# MCPv3ULN2803.net
KiCad netlist of a schematic drawn in EAGLE
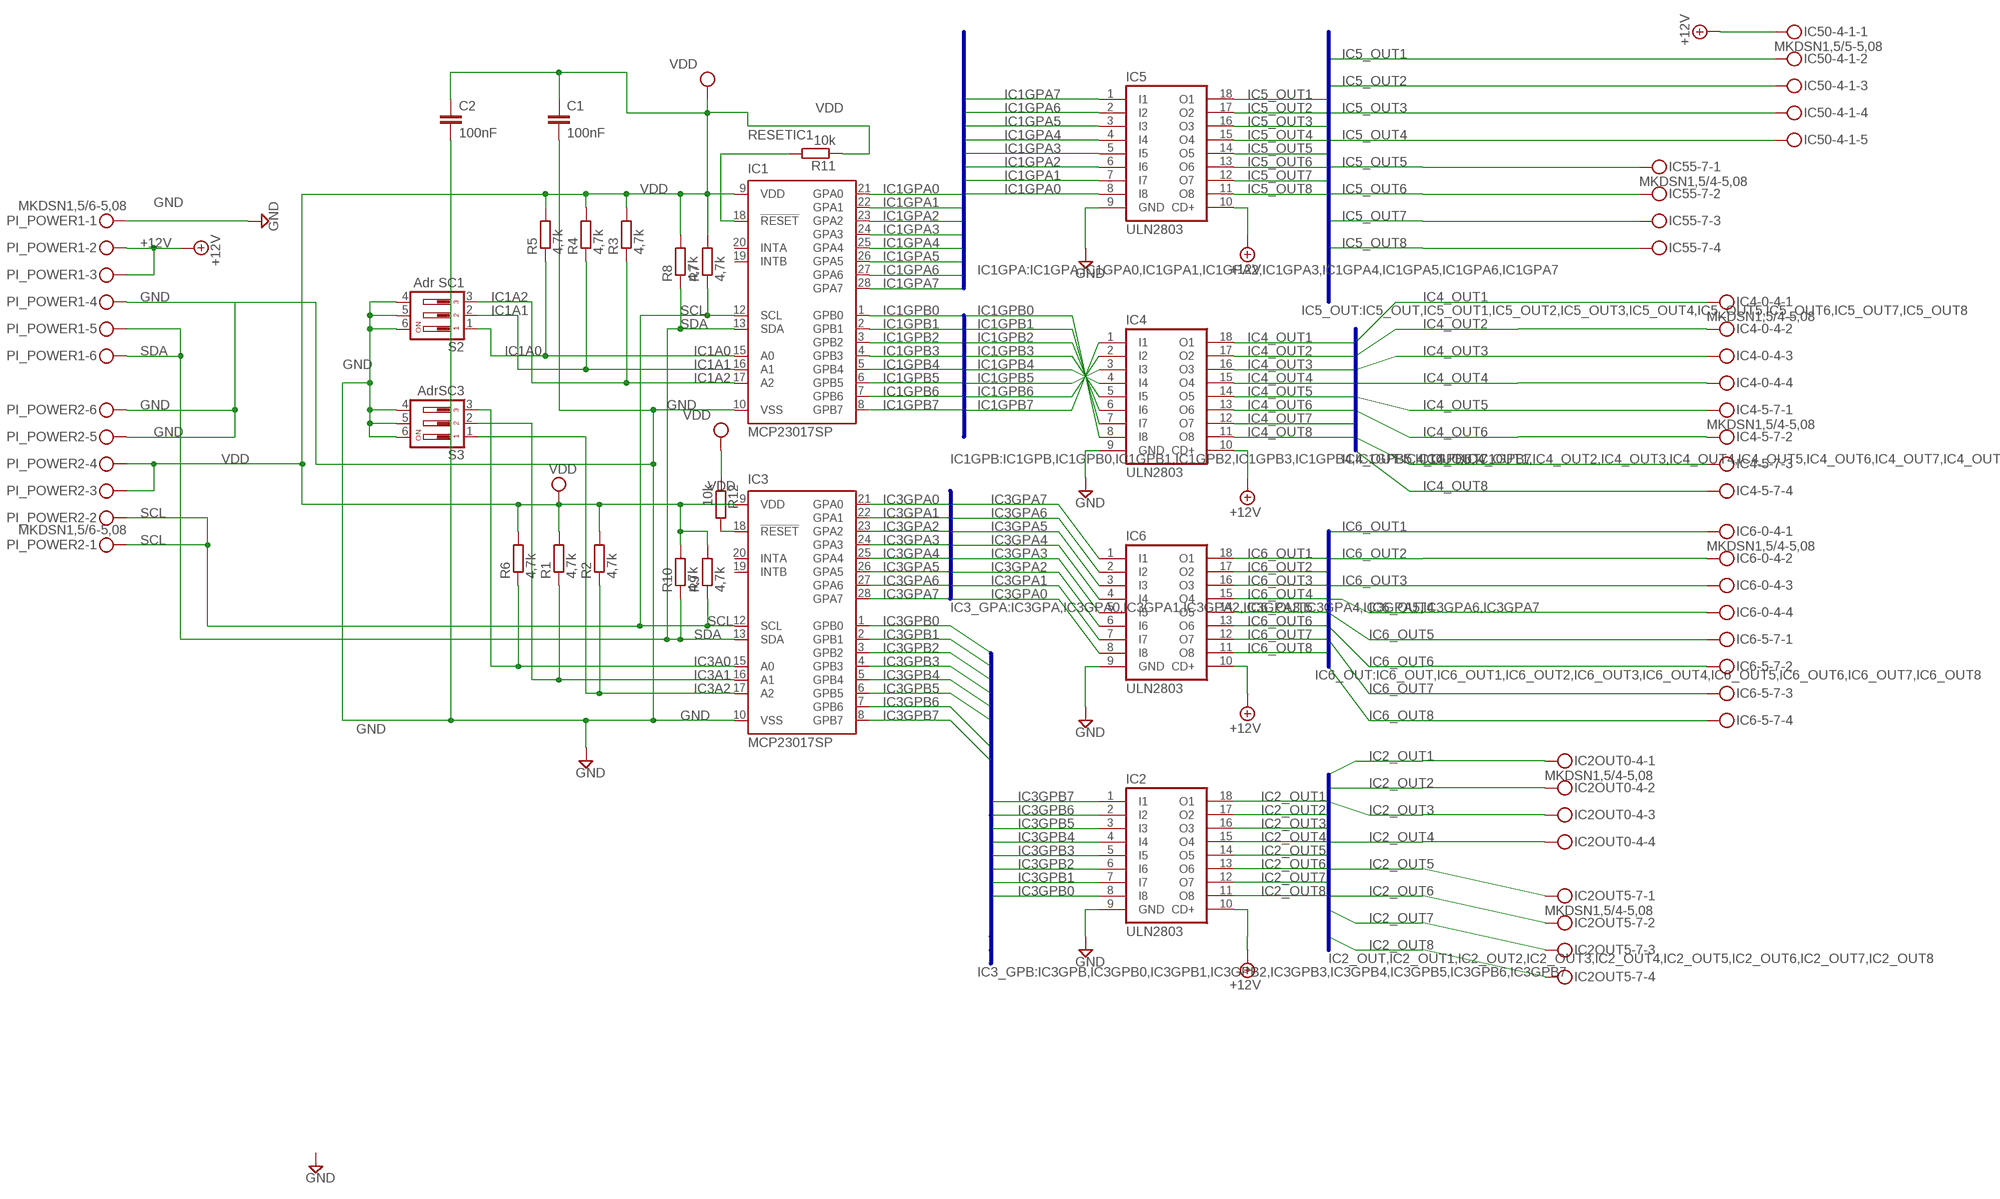
[diagram p0: schematic, sheet 1]

(export (version "E")
  (design (tool "Eeschema 10.0.6"))
  (components
    (comp (ref "C1")
      (value "100nF")
      (footprint "eagle-import:C025_050-025X075")
      (libsource (lib "eagle-import") (part "C-EU025_050-025X075"))
    )
    (comp (ref "C2")
      (value "100nF")
      (footprint "eagle-import:C025_050-025X075")
      (libsource (lib "eagle-import") (part "C-EU025_050-025X075"))
    )
    (comp (ref "IC1")
      (value "MCP23017SP")
      (footprint "eagle-import:DIL28-3")
      (fields (field (name "MF") "MICROCHIP") (field (name "MPN") "MCP23017-E/SP"))
      (libsource (lib "eagle-import") (part "MCP23017SP"))
    )
    (comp (ref "IC2")
      (value "ULN2803")
      (footprint "eagle-import:DIL18")
      (libsource (lib "eagle-import") (part "ULN2803A"))
    )
    (comp (ref "IC2OUT0-4")
      (value "MKDSN1,5/4-5,08")
      (footprint "eagle-import:MKDSN1,5_4-5,08")
      (libsource (lib "eagle-import") (part "MKDSN1,5/4-5,08"))
    )
    (comp (ref "IC2OUT5-7")
      (value "MKDSN1,5/4-5,08")
      (footprint "eagle-import:MKDSN1,5_4-5,08")
      (libsource (lib "eagle-import") (part "MKDSN1,5/4-5,08"))
    )
    (comp (ref "IC3")
      (value "MCP23017SP")
      (footprint "eagle-import:DIL28-3")
      (fields (field (name "MF") "MICROCHIP") (field (name "MPN") "MCP23017-E/SP"))
      (libsource (lib "eagle-import") (part "MCP23017SP"))
    )
    (comp (ref "IC4")
      (value "ULN2803")
      (footprint "eagle-import:DIL18")
      (libsource (lib "eagle-import") (part "ULN2803A"))
    )
    (comp (ref "IC4-0-4")
      (value "MKDSN1,5/4-5,08")
      (footprint "eagle-import:MKDSN1,5_4-5,08")
      (libsource (lib "eagle-import") (part "MKDSN1,5/4-5,08"))
    )
    (comp (ref "IC4-5-7")
      (value "MKDSN1,5/4-5,08")
      (footprint "eagle-import:MKDSN1,5_4-5,08")
      (libsource (lib "eagle-import") (part "MKDSN1,5/4-5,08"))
    )
    (comp (ref "IC5")
      (value "ULN2803")
      (footprint "eagle-import:DIL18")
      (libsource (lib "eagle-import") (part "ULN2803A"))
    )
    (comp (ref "IC6")
      (value "ULN2803")
      (footprint "eagle-import:DIL18")
      (libsource (lib "eagle-import") (part "ULN2803A"))
    )
    (comp (ref "IC6-0-4")
      (value "MKDSN1,5/4-5,08")
      (footprint "eagle-import:MKDSN1,5_4-5,08")
      (libsource (lib "eagle-import") (part "MKDSN1,5/4-5,08"))
    )
    (comp (ref "IC6-5-7")
      (value "MKDSN1,5/4-5,08")
      (footprint "eagle-import:MKDSN1,5_4-5,08")
      (libsource (lib "eagle-import") (part "MKDSN1,5/4-5,08"))
    )
    (comp (ref "IC50-4-1")
      (value "MKDSN1,5/5-5,08")
      (footprint "eagle-import:MKDSN1,5_5-5,08")
      (libsource (lib "eagle-import") (part "MKDSN1,5/5-5,08"))
    )
    (comp (ref "IC55-7")
      (value "MKDSN1,5/4-5,08")
      (footprint "eagle-import:MKDSN1,5_4-5,08")
      (libsource (lib "eagle-import") (part "MKDSN1,5/4-5,08"))
    )
    (comp (ref "PI_POWER1")
      (value "MKDSN1,5/6-5,08")
      (footprint "eagle-import:MKDSN1,5_6-5,08")
      (libsource (lib "eagle-import") (part "MKDSN1,5/6-5,08"))
    )
    (comp (ref "PI_POWER2")
      (value "MKDSN1,5/6-5,08")
      (footprint "eagle-import:MKDSN1,5_6-5,08")
      (libsource (lib "eagle-import") (part "MKDSN1,5/6-5,08"))
    )
    (comp (ref "R1")
      (value "4,7k")
      (footprint "eagle-import:0204_7")
      (libsource (lib "eagle-import") (part "R-EU_0204/7"))
    )
    (comp (ref "R2")
      (value "4,7k")
      (footprint "eagle-import:0204_7")
      (libsource (lib "eagle-import") (part "R-EU_0204/7"))
    )
    (comp (ref "R3")
      (value "4,7k")
      (footprint "eagle-import:0204_7")
      (libsource (lib "eagle-import") (part "R-EU_0204/7"))
    )
    (comp (ref "R4")
      (value "4,7k")
      (footprint "eagle-import:0204_7")
      (libsource (lib "eagle-import") (part "R-EU_0204/7"))
    )
    (comp (ref "R5")
      (value "4,7k")
      (footprint "eagle-import:0204_7")
      (libsource (lib "eagle-import") (part "R-EU_0204/7"))
    )
    (comp (ref "R6")
      (value "4,7k")
      (footprint "eagle-import:0204_7")
      (libsource (lib "eagle-import") (part "R-EU_0204/7"))
    )
    (comp (ref "R7")
      (value "4,7k")
      (footprint "eagle-import:0204_7")
      (libsource (lib "eagle-import") (part "R-EU_0204/7"))
    )
    (comp (ref "R8")
      (value "4,7k")
      (footprint "eagle-import:0204_7")
      (libsource (lib "eagle-import") (part "R-EU_0204/7"))
    )
    (comp (ref "R9")
      (value "4,7k")
      (footprint "eagle-import:0204_7")
      (libsource (lib "eagle-import") (part "R-EU_0204/7"))
    )
    (comp (ref "R10")
      (value "4,7k")
      (footprint "eagle-import:0204_7")
      (libsource (lib "eagle-import") (part "R-EU_0204/7"))
    )
    (comp (ref "R11")
      (value "10k")
      (footprint "eagle-import:0204_7")
      (libsource (lib "eagle-import") (part "R-EU_0204/7"))
    )
    (comp (ref "R12")
      (value "10k")
      (footprint "eagle-import:0204_7")
      (libsource (lib "eagle-import") (part "R-EU_0204/7"))
    )
    (comp (ref "S2")
      (value "Adr SC1")
      (footprint "eagle-import:DIP03YL")
      (libsource (lib "eagle-import") (part "DIP03YL"))
    )
    (comp (ref "S3")
      (value "AdrSC3")
      (footprint "eagle-import:DIP03YL")
      (libsource (lib "eagle-import") (part "DIP03YL"))
    )
  )
  (nets
    (net (code "7") (name "+12V") (class "Default")
      (node (ref "IC2") (pin "10") (pinfunction "CD+_10") (pintype "passive"))
      (node (ref "IC4") (pin "10") (pinfunction "CD+_10") (pintype "passive"))
      (node (ref "IC5") (pin "10") (pinfunction "CD+_10") (pintype "passive"))
      (node (ref "IC50-4-1") (pin "1") (pinfunction "KL_1") (pintype "passive"))
      (node (ref "IC6") (pin "10") (pinfunction "CD+_10") (pintype "passive"))
      (node (ref "PI_POWER1") (pin "2") (pinfunction "KL_2") (pintype "passive"))
      (node (ref "PI_POWER1") (pin "3") (pinfunction "KL_3") (pintype "passive"))
    )
    (net (code "8") (name "/IC1A0") (class "Default")
      (node (ref "IC1") (pin "15") (pinfunction "A0_15") (pintype "input"))
      (node (ref "R5") (pin "1") (pinfunction "1_1") (pintype "passive"))
      (node (ref "S2") (pin "1") (pinfunction "1_1") (pintype "passive"))
    )
    (net (code "9") (name "/IC1A1") (class "Default")
      (node (ref "IC1") (pin "16") (pinfunction "A1_16") (pintype "input"))
      (node (ref "R4") (pin "1") (pinfunction "1_1") (pintype "passive"))
      (node (ref "S2") (pin "2") (pinfunction "2_2") (pintype "passive"))
    )
    (net (code "10") (name "/IC1A2") (class "Default")
      (node (ref "IC1") (pin "17") (pinfunction "A2_17") (pintype "input"))
      (node (ref "R3") (pin "1") (pinfunction "1_1") (pintype "passive"))
      (node (ref "S2") (pin "3") (pinfunction "3_3") (pintype "passive"))
    )
    (net (code "11") (name "/IC1GPA0") (class "Default")
      (node (ref "IC1") (pin "21") (pinfunction "GPA0_21") (pintype "bidirectional"))
      (node (ref "IC5") (pin "8") (pinfunction "I8_8") (pintype "input"))
    )
    (net (code "12") (name "/IC1GPA1") (class "Default")
      (node (ref "IC1") (pin "22") (pinfunction "GPA1_22") (pintype "bidirectional"))
      (node (ref "IC5") (pin "7") (pinfunction "I7_7") (pintype "input"))
    )
    (net (code "13") (name "/IC1GPA2") (class "Default")
      (node (ref "IC1") (pin "23") (pinfunction "GPA2_23") (pintype "bidirectional"))
      (node (ref "IC5") (pin "6") (pinfunction "I6_6") (pintype "input"))
    )
    (net (code "14") (name "/IC1GPA3") (class "Default")
      (node (ref "IC1") (pin "24") (pinfunction "GPA3_24") (pintype "bidirectional"))
      (node (ref "IC5") (pin "5") (pinfunction "I5_5") (pintype "input"))
    )
    (net (code "15") (name "/IC1GPA4") (class "Default")
      (node (ref "IC1") (pin "25") (pinfunction "GPA4_25") (pintype "bidirectional"))
      (node (ref "IC5") (pin "4") (pinfunction "I4_4") (pintype "input"))
    )
    (net (code "16") (name "/IC1GPA5") (class "Default")
      (node (ref "IC1") (pin "26") (pinfunction "GPA5_26") (pintype "bidirectional"))
      (node (ref "IC5") (pin "3") (pinfunction "I3_3") (pintype "input"))
    )
    (net (code "17") (name "/IC1GPA6") (class "Default")
      (node (ref "IC1") (pin "27") (pinfunction "GPA6_27") (pintype "bidirectional"))
      (node (ref "IC5") (pin "2") (pinfunction "I2_2") (pintype "input"))
    )
    (net (code "18") (name "/IC1GPA7") (class "Default")
      (node (ref "IC1") (pin "28") (pinfunction "GPA7_28") (pintype "bidirectional"))
      (node (ref "IC5") (pin "1") (pinfunction "I1_1") (pintype "input"))
    )
    (net (code "19") (name "/IC1GPB0") (class "Default")
      (node (ref "IC1") (pin "1") (pinfunction "GPB0_1") (pintype "bidirectional"))
      (node (ref "IC4") (pin "8") (pinfunction "I8_8") (pintype "input"))
    )
    (net (code "20") (name "/IC1GPB1") (class "Default")
      (node (ref "IC1") (pin "2") (pinfunction "GPB1_2") (pintype "bidirectional"))
      (node (ref "IC4") (pin "7") (pinfunction "I7_7") (pintype "input"))
    )
    (net (code "21") (name "/IC1GPB2") (class "Default")
      (node (ref "IC1") (pin "3") (pinfunction "GPB2_3") (pintype "bidirectional"))
      (node (ref "IC4") (pin "6") (pinfunction "I6_6") (pintype "input"))
    )
    (net (code "22") (name "/IC1GPB3") (class "Default")
      (node (ref "IC1") (pin "4") (pinfunction "GPB3_4") (pintype "bidirectional"))
      (node (ref "IC4") (pin "5") (pinfunction "I5_5") (pintype "input"))
    )
    (net (code "23") (name "/IC1GPB4") (class "Default")
      (node (ref "IC1") (pin "5") (pinfunction "GPB4_5") (pintype "bidirectional"))
      (node (ref "IC4") (pin "4") (pinfunction "I4_4") (pintype "input"))
    )
    (net (code "24") (name "/IC1GPB5") (class "Default")
      (node (ref "IC1") (pin "6") (pinfunction "GPB5_6") (pintype "bidirectional"))
      (node (ref "IC4") (pin "3") (pinfunction "I3_3") (pintype "input"))
    )
    (net (code "25") (name "/IC1GPB6") (class "Default")
      (node (ref "IC1") (pin "7") (pinfunction "GPB6_7") (pintype "bidirectional"))
      (node (ref "IC4") (pin "2") (pinfunction "I2_2") (pintype "input"))
    )
    (net (code "26") (name "/IC1GPB7") (class "Default")
      (node (ref "IC1") (pin "8") (pinfunction "GPB7_8") (pintype "bidirectional"))
      (node (ref "IC4") (pin "1") (pinfunction "I1_1") (pintype "input"))
    )
    (net (code "27") (name "/IC2_OUT1") (class "Default")
      (node (ref "IC2") (pin "18") (pinfunction "O1_18") (pintype "open_collector"))
      (node (ref "IC2OUT0-4") (pin "1") (pinfunction "KL_1") (pintype "passive"))
    )
    (net (code "28") (name "/IC2_OUT2") (class "Default")
      (node (ref "IC2") (pin "17") (pinfunction "O2_17") (pintype "open_collector"))
      (node (ref "IC2OUT0-4") (pin "2") (pinfunction "KL_2") (pintype "passive"))
    )
    (net (code "29") (name "/IC2_OUT3") (class "Default")
      (node (ref "IC2") (pin "16") (pinfunction "O3_16") (pintype "open_collector"))
      (node (ref "IC2OUT0-4") (pin "3") (pinfunction "KL_3") (pintype "passive"))
    )
    (net (code "30") (name "/IC2_OUT4") (class "Default")
      (node (ref "IC2") (pin "15") (pinfunction "O4_15") (pintype "open_collector"))
      (node (ref "IC2OUT0-4") (pin "4") (pinfunction "KL_4") (pintype "passive"))
    )
    (net (code "31") (name "/IC2_OUT5") (class "Default")
      (node (ref "IC2") (pin "14") (pinfunction "O5_14") (pintype "open_collector"))
      (node (ref "IC2OUT5-7") (pin "1") (pinfunction "KL_1") (pintype "passive"))
    )
    (net (code "32") (name "/IC2_OUT6") (class "Default")
      (node (ref "IC2") (pin "13") (pinfunction "O6_13") (pintype "open_collector"))
      (node (ref "IC2OUT5-7") (pin "2") (pinfunction "KL_2") (pintype "passive"))
    )
    (net (code "33") (name "/IC2_OUT7") (class "Default")
      (node (ref "IC2") (pin "12") (pinfunction "O7_12") (pintype "open_collector"))
      (node (ref "IC2OUT5-7") (pin "3") (pinfunction "KL_3") (pintype "passive"))
    )
    (net (code "34") (name "/IC2_OUT8") (class "Default")
      (node (ref "IC2") (pin "11") (pinfunction "O8_11") (pintype "open_collector"))
      (node (ref "IC2OUT5-7") (pin "4") (pinfunction "KL_4") (pintype "passive"))
    )
    (net (code "35") (name "/IC3A0") (class "Default")
      (node (ref "IC3") (pin "15") (pinfunction "A0_15") (pintype "input"))
      (node (ref "R6") (pin "1") (pinfunction "1_1") (pintype "passive"))
      (node (ref "S3") (pin "3") (pinfunction "3_3") (pintype "passive"))
    )
    (net (code "36") (name "/IC3A1") (class "Default")
      (node (ref "IC3") (pin "16") (pinfunction "A1_16") (pintype "input"))
      (node (ref "R1") (pin "1") (pinfunction "1_1") (pintype "passive"))
      (node (ref "S3") (pin "2") (pinfunction "2_2") (pintype "passive"))
    )
    (net (code "37") (name "/IC3A2") (class "Default")
      (node (ref "IC3") (pin "17") (pinfunction "A2_17") (pintype "input"))
      (node (ref "R2") (pin "1") (pinfunction "1_1") (pintype "passive"))
      (node (ref "S3") (pin "1") (pinfunction "1_1") (pintype "passive"))
    )
    (net (code "38") (name "/IC3GPA0") (class "Default")
      (node (ref "IC3") (pin "21") (pinfunction "GPA0_21") (pintype "bidirectional"))
      (node (ref "IC6") (pin "8") (pinfunction "I8_8") (pintype "input"))
    )
    (net (code "39") (name "/IC3GPA1") (class "Default")
      (node (ref "IC3") (pin "22") (pinfunction "GPA1_22") (pintype "bidirectional"))
      (node (ref "IC6") (pin "7") (pinfunction "I7_7") (pintype "input"))
    )
    (net (code "40") (name "/IC3GPA2") (class "Default")
      (node (ref "IC3") (pin "23") (pinfunction "GPA2_23") (pintype "bidirectional"))
      (node (ref "IC6") (pin "6") (pinfunction "I6_6") (pintype "input"))
    )
    (net (code "41") (name "/IC3GPA3") (class "Default")
      (node (ref "IC3") (pin "24") (pinfunction "GPA3_24") (pintype "bidirectional"))
      (node (ref "IC6") (pin "5") (pinfunction "I5_5") (pintype "input"))
    )
    (net (code "42") (name "/IC3GPA4") (class "Default")
      (node (ref "IC3") (pin "25") (pinfunction "GPA4_25") (pintype "bidirectional"))
      (node (ref "IC6") (pin "4") (pinfunction "I4_4") (pintype "input"))
    )
    (net (code "43") (name "/IC3GPA5") (class "Default")
      (node (ref "IC3") (pin "26") (pinfunction "GPA5_26") (pintype "bidirectional"))
      (node (ref "IC6") (pin "3") (pinfunction "I3_3") (pintype "input"))
    )
    (net (code "44") (name "/IC3GPA6") (class "Default")
      (node (ref "IC3") (pin "27") (pinfunction "GPA6_27") (pintype "bidirectional"))
      (node (ref "IC6") (pin "2") (pinfunction "I2_2") (pintype "input"))
    )
    (net (code "45") (name "/IC3GPA7") (class "Default")
      (node (ref "IC3") (pin "28") (pinfunction "GPA7_28") (pintype "bidirectional"))
      (node (ref "IC6") (pin "1") (pinfunction "I1_1") (pintype "input"))
    )
    (net (code "46") (name "/IC3GPB0") (class "Default")
      (node (ref "IC2") (pin "8") (pinfunction "I8_8") (pintype "input"))
      (node (ref "IC3") (pin "1") (pinfunction "GPB0_1") (pintype "bidirectional"))
    )
    (net (code "47") (name "/IC3GPB1") (class "Default")
      (node (ref "IC2") (pin "7") (pinfunction "I7_7") (pintype "input"))
      (node (ref "IC3") (pin "2") (pinfunction "GPB1_2") (pintype "bidirectional"))
    )
    (net (code "48") (name "/IC3GPB2") (class "Default")
      (node (ref "IC2") (pin "6") (pinfunction "I6_6") (pintype "input"))
      (node (ref "IC3") (pin "3") (pinfunction "GPB2_3") (pintype "bidirectional"))
    )
    (net (code "49") (name "/IC3GPB3") (class "Default")
      (node (ref "IC2") (pin "5") (pinfunction "I5_5") (pintype "input"))
      (node (ref "IC3") (pin "4") (pinfunction "GPB3_4") (pintype "bidirectional"))
    )
    (net (code "50") (name "/IC3GPB4") (class "Default")
      (node (ref "IC2") (pin "4") (pinfunction "I4_4") (pintype "input"))
      (node (ref "IC3") (pin "5") (pinfunction "GPB4_5") (pintype "bidirectional"))
    )
    (net (code "51") (name "/IC3GPB5") (class "Default")
      (node (ref "IC2") (pin "3") (pinfunction "I3_3") (pintype "input"))
      (node (ref "IC3") (pin "6") (pinfunction "GPB5_6") (pintype "bidirectional"))
    )
    (net (code "52") (name "/IC3GPB6") (class "Default")
      (node (ref "IC2") (pin "2") (pinfunction "I2_2") (pintype "input"))
      (node (ref "IC3") (pin "7") (pinfunction "GPB6_7") (pintype "bidirectional"))
    )
    (net (code "53") (name "/IC3GPB7") (class "Default")
      (node (ref "IC2") (pin "1") (pinfunction "I1_1") (pintype "input"))
      (node (ref "IC3") (pin "8") (pinfunction "GPB7_8") (pintype "bidirectional"))
    )
    (net (code "54") (name "/IC4_OUT1") (class "Default")
      (node (ref "IC4") (pin "18") (pinfunction "O1_18") (pintype "open_collector"))
      (node (ref "IC4-0-4") (pin "1") (pinfunction "KL_1") (pintype "passive"))
    )
    (net (code "55") (name "/IC4_OUT2") (class "Default")
      (node (ref "IC4") (pin "17") (pinfunction "O2_17") (pintype "open_collector"))
      (node (ref "IC4-0-4") (pin "2") (pinfunction "KL_2") (pintype "passive"))
    )
    (net (code "56") (name "/IC4_OUT3") (class "Default")
      (node (ref "IC4") (pin "16") (pinfunction "O3_16") (pintype "open_collector"))
      (node (ref "IC4-0-4") (pin "3") (pinfunction "KL_3") (pintype "passive"))
    )
    (net (code "57") (name "/IC4_OUT4") (class "Default")
      (node (ref "IC4") (pin "15") (pinfunction "O4_15") (pintype "open_collector"))
      (node (ref "IC4-0-4") (pin "4") (pinfunction "KL_4") (pintype "passive"))
    )
    (net (code "58") (name "/IC4_OUT5") (class "Default")
      (node (ref "IC4") (pin "14") (pinfunction "O5_14") (pintype "open_collector"))
      (node (ref "IC4-5-7") (pin "1") (pinfunction "KL_1") (pintype "passive"))
    )
    (net (code "59") (name "/IC4_OUT6") (class "Default")
      (node (ref "IC4") (pin "13") (pinfunction "O6_13") (pintype "open_collector"))
      (node (ref "IC4-5-7") (pin "2") (pinfunction "KL_2") (pintype "passive"))
    )
    (net (code "60") (name "/IC4_OUT7") (class "Default")
      (node (ref "IC4") (pin "12") (pinfunction "O7_12") (pintype "open_collector"))
      (node (ref "IC4-5-7") (pin "3") (pinfunction "KL_3") (pintype "passive"))
    )
    (net (code "61") (name "/IC4_OUT8") (class "Default")
      (node (ref "IC4") (pin "11") (pinfunction "O8_11") (pintype "open_collector"))
      (node (ref "IC4-5-7") (pin "4") (pinfunction "KL_4") (pintype "passive"))
    )
    (net (code "62") (name "/IC5_OUT1") (class "Default")
      (node (ref "IC5") (pin "18") (pinfunction "O1_18") (pintype "open_collector"))
      (node (ref "IC50-4-1") (pin "2") (pinfunction "KL_2") (pintype "passive"))
    )
    (net (code "63") (name "/IC5_OUT2") (class "Default")
      (node (ref "IC5") (pin "17") (pinfunction "O2_17") (pintype "open_collector"))
      (node (ref "IC50-4-1") (pin "3") (pinfunction "KL_3") (pintype "passive"))
    )
    (net (code "64") (name "/IC5_OUT3") (class "Default")
      (node (ref "IC5") (pin "16") (pinfunction "O3_16") (pintype "open_collector"))
      (node (ref "IC50-4-1") (pin "4") (pinfunction "KL_4") (pintype "passive"))
    )
    (net (code "65") (name "/IC5_OUT4") (class "Default")
      (node (ref "IC5") (pin "15") (pinfunction "O4_15") (pintype "open_collector"))
      (node (ref "IC50-4-1") (pin "5") (pinfunction "KL_5") (pintype "passive"))
    )
    (net (code "66") (name "/IC5_OUT5") (class "Default")
      (node (ref "IC5") (pin "14") (pinfunction "O5_14") (pintype "open_collector"))
      (node (ref "IC55-7") (pin "1") (pinfunction "KL_1") (pintype "passive"))
    )
    (net (code "67") (name "/IC5_OUT6") (class "Default")
      (node (ref "IC5") (pin "13") (pinfunction "O6_13") (pintype "open_collector"))
      (node (ref "IC55-7") (pin "2") (pinfunction "KL_2") (pintype "passive"))
    )
    (net (code "68") (name "/IC5_OUT7") (class "Default")
      (node (ref "IC5") (pin "12") (pinfunction "O7_12") (pintype "open_collector"))
      (node (ref "IC55-7") (pin "3") (pinfunction "KL_3") (pintype "passive"))
    )
    (net (code "69") (name "/IC5_OUT8") (class "Default")
      (node (ref "IC5") (pin "11") (pinfunction "O8_11") (pintype "open_collector"))
      (node (ref "IC55-7") (pin "4") (pinfunction "KL_4") (pintype "passive"))
    )
    (net (code "70") (name "/IC6_OUT1") (class "Default")
      (node (ref "IC6") (pin "18") (pinfunction "O1_18") (pintype "open_collector"))
      (node (ref "IC6-0-4") (pin "1") (pinfunction "KL_1") (pintype "passive"))
    )
    (net (code "71") (name "/IC6_OUT2") (class "Default")
      (node (ref "IC6") (pin "17") (pinfunction "O2_17") (pintype "open_collector"))
      (node (ref "IC6-0-4") (pin "2") (pinfunction "KL_2") (pintype "passive"))
    )
    (net (code "72") (name "/IC6_OUT3") (class "Default")
      (node (ref "IC6") (pin "16") (pinfunction "O3_16") (pintype "open_collector"))
      (node (ref "IC6-0-4") (pin "3") (pinfunction "KL_3") (pintype "passive"))
    )
    (net (code "73") (name "/IC6_OUT4") (class "Default")
      (node (ref "IC6") (pin "15") (pinfunction "O4_15") (pintype "open_collector"))
      (node (ref "IC6-0-4") (pin "4") (pinfunction "KL_4") (pintype "passive"))
    )
    (net (code "74") (name "/IC6_OUT5") (class "Default")
      (node (ref "IC6") (pin "14") (pinfunction "O5_14") (pintype "open_collector"))
      (node (ref "IC6-5-7") (pin "1") (pinfunction "KL_1") (pintype "passive"))
    )
    (net (code "75") (name "/IC6_OUT6") (class "Default")
      (node (ref "IC6") (pin "13") (pinfunction "O6_13") (pintype "open_collector"))
      (node (ref "IC6-5-7") (pin "2") (pinfunction "KL_2") (pintype "passive"))
    )
    (net (code "76") (name "/IC6_OUT7") (class "Default")
      (node (ref "IC6") (pin "12") (pinfunction "O7_12") (pintype "open_collector"))
      (node (ref "IC6-5-7") (pin "3") (pinfunction "KL_3") (pintype "passive"))
    )
    (net (code "77") (name "/IC6_OUT8") (class "Default")
      (node (ref "IC6") (pin "11") (pinfunction "O8_11") (pintype "open_collector"))
      (node (ref "IC6-5-7") (pin "4") (pinfunction "KL_4") (pintype "passive"))
    )
    (net (code "78") (name "/RESETIC1") (class "Default")
      (node (ref "IC1") (pin "18") (pinfunction "~{RESET}_18") (pintype "input"))
      (node (ref "R11") (pin "2") (pinfunction "2_2") (pintype "passive"))
    )
    (net (code "79") (name "/SCL") (class "Default")
      (node (ref "IC1") (pin "12") (pinfunction "SCL_12") (pintype "input"))
      (node (ref "IC3") (pin "12") (pinfunction "SCL_12") (pintype "input"))
      (node (ref "PI_POWER2") (pin "1") (pinfunction "KL_1") (pintype "passive"))
      (node (ref "PI_POWER2") (pin "2") (pinfunction "KL_2") (pintype "passive"))
      (node (ref "R7") (pin "1") (pinfunction "1_1") (pintype "passive"))
      (node (ref "R9") (pin "1") (pinfunction "1_1") (pintype "passive"))
    )
    (net (code "80") (name "/SDA") (class "Default")
      (node (ref "IC1") (pin "13") (pinfunction "SDA_13") (pintype "bidirectional"))
      (node (ref "IC3") (pin "13") (pinfunction "SDA_13") (pintype "bidirectional"))
      (node (ref "PI_POWER1") (pin "5") (pinfunction "KL_5") (pintype "passive"))
      (node (ref "PI_POWER1") (pin "6") (pinfunction "KL_6") (pintype "passive"))
      (node (ref "R10") (pin "1") (pinfunction "1_1") (pintype "passive"))
      (node (ref "R8") (pin "1") (pinfunction "1_1") (pintype "passive"))
    )
    (net (code "87") (name "GND") (class "Default")
      (node (ref "C1") (pin "2") (pinfunction "2_2") (pintype "passive"))
      (node (ref "C2") (pin "2") (pinfunction "2_2") (pintype "passive"))
      (node (ref "IC1") (pin "10") (pinfunction "VSS_10") (pintype "power_in"))
      (node (ref "IC2") (pin "9") (pinfunction "GND_9") (pintype "power_in"))
      (node (ref "IC3") (pin "10") (pinfunction "VSS_10") (pintype "power_in"))
      (node (ref "IC4") (pin "9") (pinfunction "GND_9") (pintype "power_in"))
      (node (ref "IC5") (pin "9") (pinfunction "GND_9") (pintype "power_in"))
      (node (ref "IC6") (pin "9") (pinfunction "GND_9") (pintype "power_in"))
      (node (ref "PI_POWER1") (pin "1") (pinfunction "KL_1") (pintype "passive"))
      (node (ref "PI_POWER1") (pin "4") (pinfunction "KL_4") (pintype "passive"))
      (node (ref "PI_POWER2") (pin "5") (pinfunction "KL_5") (pintype "passive"))
      (node (ref "PI_POWER2") (pin "6") (pinfunction "KL_6") (pintype "passive"))
      (node (ref "S2") (pin "4") (pinfunction "4_4") (pintype "passive"))
      (node (ref "S2") (pin "5") (pinfunction "5_5") (pintype "passive"))
      (node (ref "S2") (pin "6") (pinfunction "6_6") (pintype "passive"))
      (node (ref "S3") (pin "4") (pinfunction "4_4") (pintype "passive"))
      (node (ref "S3") (pin "5") (pinfunction "5_5") (pintype "passive"))
      (node (ref "S3") (pin "6") (pinfunction "6_6") (pintype "passive"))
    )
    (net (code "88") (name "Net-(IC3-~{RESET})") (class "Default")
      (node (ref "IC3") (pin "18") (pinfunction "~{RESET}_18") (pintype "input"))
      (node (ref "R12") (pin "2") (pinfunction "2_2") (pintype "passive"))
    )
    (net (code "89") (name "VDD") (class "Default")
      (node (ref "C1") (pin "1") (pinfunction "1_1") (pintype "passive"))
      (node (ref "C2") (pin "1") (pinfunction "1_1") (pintype "passive"))
      (node (ref "IC1") (pin "9") (pinfunction "VDD_9") (pintype "power_in"))
      (node (ref "IC3") (pin "9") (pinfunction "VDD_9") (pintype "power_in"))
      (node (ref "PI_POWER2") (pin "3") (pinfunction "KL_3") (pintype "passive"))
      (node (ref "PI_POWER2") (pin "4") (pinfunction "KL_4") (pintype "passive"))
      (node (ref "R1") (pin "2") (pinfunction "2_2") (pintype "passive"))
      (node (ref "R10") (pin "2") (pinfunction "2_2") (pintype "passive"))
      (node (ref "R11") (pin "1") (pinfunction "1_1") (pintype "passive"))
      (node (ref "R12") (pin "1") (pinfunction "1_1") (pintype "passive"))
      (node (ref "R2") (pin "2") (pinfunction "2_2") (pintype "passive"))
      (node (ref "R3") (pin "2") (pinfunction "2_2") (pintype "passive"))
      (node (ref "R4") (pin "2") (pinfunction "2_2") (pintype "passive"))
      (node (ref "R5") (pin "2") (pinfunction "2_2") (pintype "passive"))
      (node (ref "R6") (pin "2") (pinfunction "2_2") (pintype "passive"))
      (node (ref "R7") (pin "2") (pinfunction "2_2") (pintype "passive"))
      (node (ref "R8") (pin "2") (pinfunction "2_2") (pintype "passive"))
      (node (ref "R9") (pin "2") (pinfunction "2_2") (pintype "passive"))
    )
    (net (code "90") (name "unconnected-(IC1-INTA-Pad20)") (class "Default")
      (node (ref "IC1") (pin "20") (pinfunction "INTA_20") (pintype "output"))
    )
    (net (code "91") (name "unconnected-(IC1-INTB-Pad19)") (class "Default")
      (node (ref "IC1") (pin "19") (pinfunction "INTB_19") (pintype "output"))
    )
    (net (code "92") (name "unconnected-(IC3-INTA-Pad20)") (class "Default")
      (node (ref "IC3") (pin "20") (pinfunction "INTA_20") (pintype "output"))
    )
    (net (code "93") (name "unconnected-(IC3-INTB-Pad19)") (class "Default")
      (node (ref "IC3") (pin "19") (pinfunction "INTB_19") (pintype "output"))
    )
  )
)
